# MJ828_-_prod.net
KiCad netlist of a schematic drawn in EAGLE
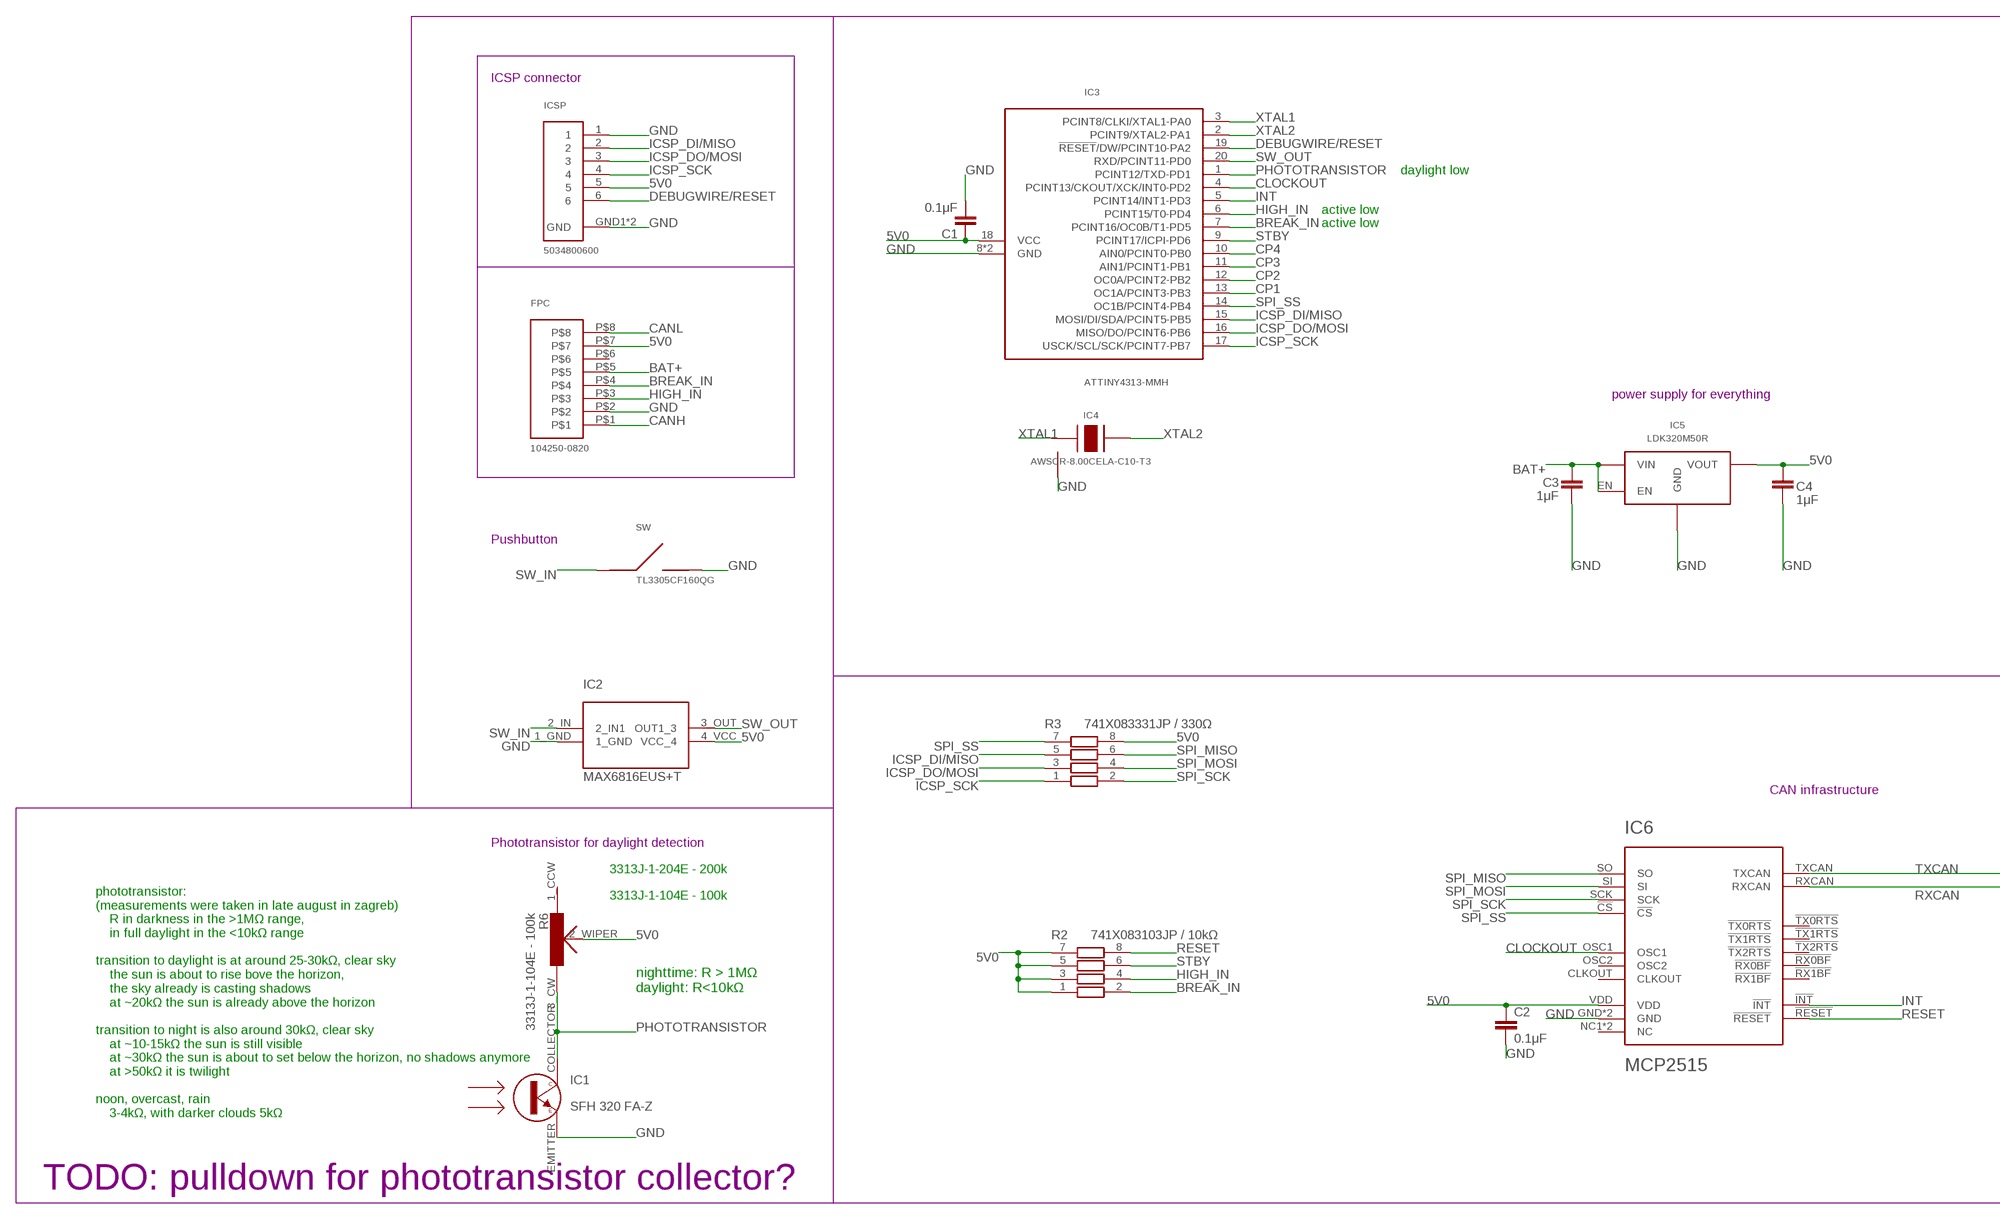
[diagram p0: schematic, sheet 1, part 1 of 2]
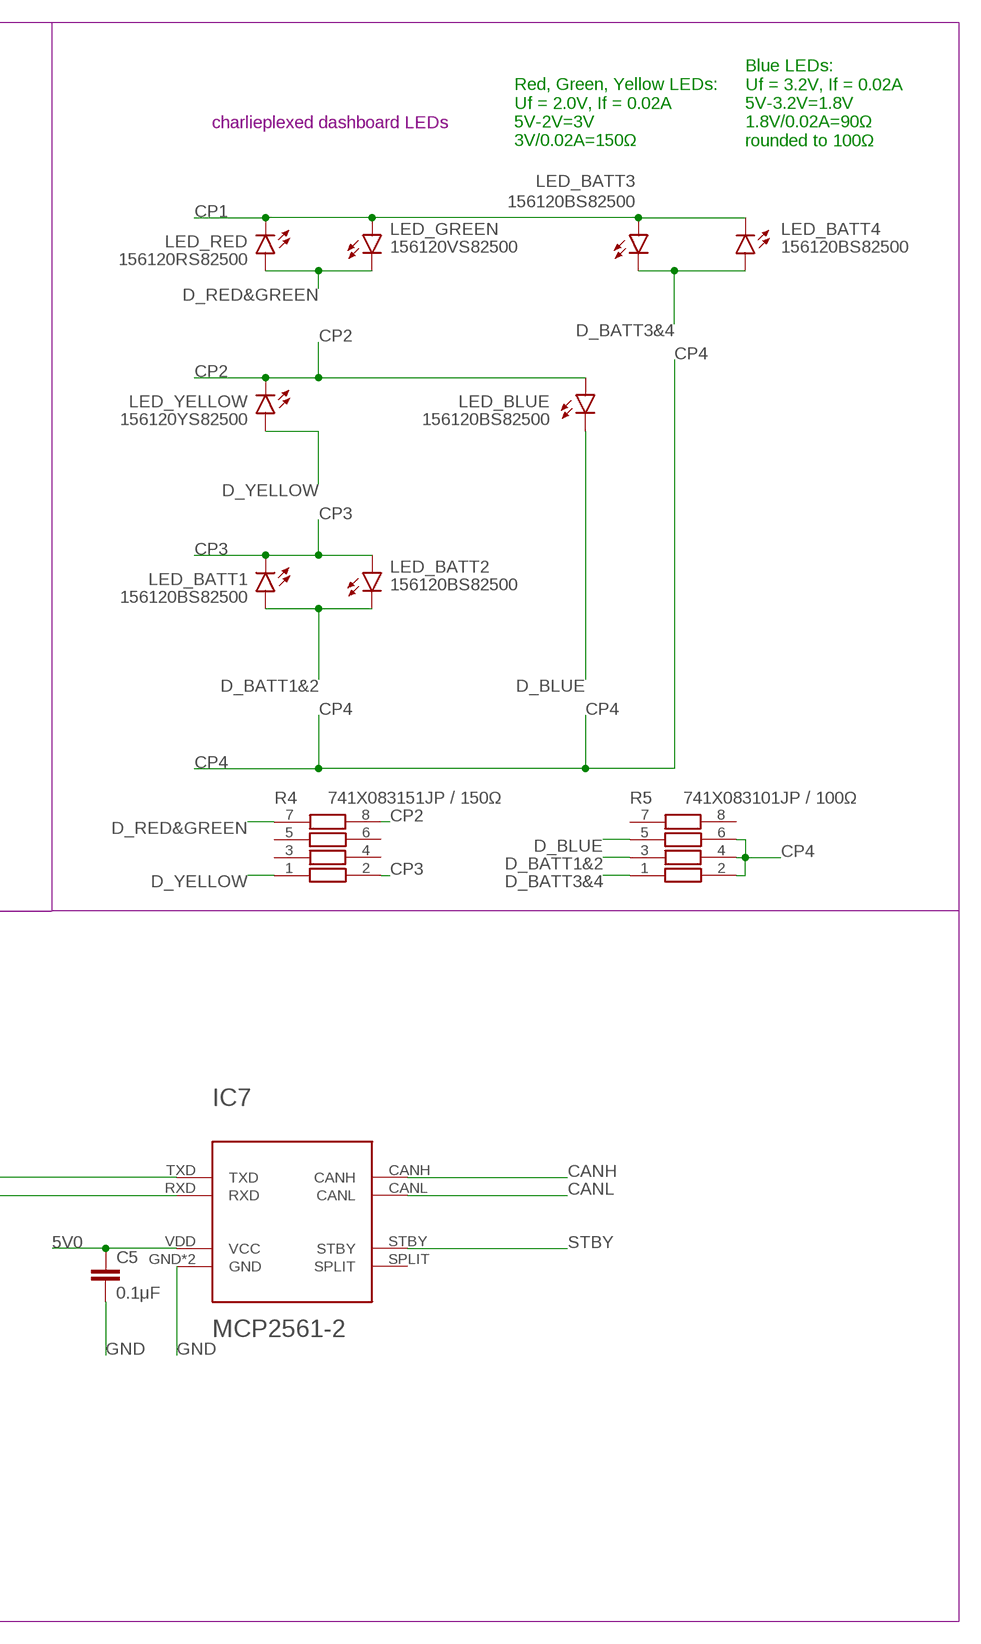
[diagram p1: schematic, sheet 1, part 2 of 2]

(export (version "E")
  (design (tool "Eeschema 10.0.6"))
  (components
    (comp (ref "C1")
      (value "0.1μF")
      (footprint "eagle-import:C0402")
      (libsource (lib "eagle-import") (part "C-EUC0402"))
    )
    (comp (ref "C2")
      (value "0.1μF")
      (footprint "eagle-import:C0402")
      (libsource (lib "eagle-import") (part "C-EUC0402"))
    )
    (comp (ref "C3")
      (value "1μF")
      (footprint "eagle-import:C0402")
      (libsource (lib "eagle-import") (part "C-EUC0402"))
    )
    (comp (ref "C4")
      (value "1μF")
      (footprint "eagle-import:C0402")
      (libsource (lib "eagle-import") (part "C-EUC0402"))
    )
    (comp (ref "C5")
      (value "0.1μF")
      (footprint "eagle-import:C0402")
      (libsource (lib "eagle-import") (part "C-EUC0402"))
    )
    (comp (ref "FPC")
      (value "104250-0820")
      (footprint "eagle-import:SMD")
      (libsource (lib "eagle-import") (part "104250-0820"))
    )
    (comp (ref "IC1")
      (value "SFH 320 FA-Z")
      (footprint "eagle-import:P-LCC-2")
      (libsource (lib "eagle-import") (part "SFH320FA"))
    )
    (comp (ref "IC2")
      (value "MAX6816EUS+T")
      (footprint "eagle-import:4SOT143")
      (libsource (lib "eagle-import") (part "MAX6816"))
    )
    (comp (ref "IC3")
      (value "ATTINY4313-MMH")
      (footprint "eagle-import:VQFN-20")
      (fields (field (name "SPICEPREFIX") "X"))
      (libsource (lib "eagle-import") (part "ATTINY4313VQFN-20"))
    )
    (comp (ref "IC4")
      (value "AWSCR-8.00CELA-C10-T3")
      (footprint "eagle-import:SMT")
      (libsource (lib "eagle-import") (part "PRQV"))
    )
    (comp (ref "IC5")
      (value "LDK320M50R")
      (footprint "eagle-import:SOT-23-5L")
      (libsource (lib "eagle-import") (part "LDK320SOT-23-5L"))
    )
    (comp (ref "IC6")
      (value "MCP2515")
      (footprint "eagle-import:QFN20")
      (libsource (lib "eagle-import") (part "MCP2515-I-ML"))
    )
    (comp (ref "IC7")
      (value "MCP2561-2")
      (footprint "eagle-import:DFN10")
      (libsource (lib "eagle-import") (part "MCP2561-2"))
    )
    (comp (ref "ICSP")
      (value "5034800600")
      (footprint "eagle-import:SMT")
      (libsource (lib "eagle-import") (part "5034800600"))
    )
    (comp (ref "LED_BATT1")
      (value "156120BS82500")
      (footprint "eagle-import:SML1206")
      (libsource (lib "eagle-import") (part "LEDSML1206"))
    )
    (comp (ref "LED_BATT2")
      (value "156120BS82500")
      (footprint "eagle-import:SML1206")
      (libsource (lib "eagle-import") (part "LEDSML1206"))
    )
    (comp (ref "LED_BATT3")
      (value "156120BS82500")
      (footprint "eagle-import:SML1206")
      (libsource (lib "eagle-import") (part "LEDSML1206"))
    )
    (comp (ref "LED_BATT4")
      (value "156120BS82500")
      (footprint "eagle-import:SML1206")
      (libsource (lib "eagle-import") (part "LEDSML1206"))
    )
    (comp (ref "LED_BLUE")
      (value "156120BS82500")
      (footprint "eagle-import:SML1206")
      (libsource (lib "eagle-import") (part "LEDSML1206"))
    )
    (comp (ref "LED_GREEN")
      (value "156120VS82500")
      (footprint "eagle-import:SML1206")
      (libsource (lib "eagle-import") (part "LEDSML1206"))
    )
    (comp (ref "LED_RED")
      (value "156120RS82500")
      (footprint "eagle-import:SML1206")
      (libsource (lib "eagle-import") (part "LEDSML1206"))
    )
    (comp (ref "LED_YELLOW")
      (value "156120YS82500")
      (footprint "eagle-import:SML1206")
      (libsource (lib "eagle-import") (part "LEDSML1206"))
    )
    (comp (ref "R2")
      (value "741X083103JP / 10kΩ")
      (footprint "eagle-import:0402")
      (libsource (lib "eagle-import") (part "741X083331JP"))
    )
    (comp (ref "R3")
      (value "741X083331JP / 330Ω")
      (footprint "eagle-import:0402")
      (libsource (lib "eagle-import") (part "741X083331JP"))
    )
    (comp (ref "R4")
      (value "741X083151JP / 150Ω")
      (footprint "eagle-import:0402")
      (libsource (lib "eagle-import") (part "741X083331JP"))
    )
    (comp (ref "R5")
      (value "741X083101JP / 100Ω")
      (footprint "eagle-import:0402")
      (libsource (lib "eagle-import") (part "741X083331JP"))
    )
    (comp (ref "R6")
      (value "3313J-1-104E - 100k")
      (footprint "eagle-import:3313")
      (libsource (lib "eagle-import") (part "3313"))
    )
    (comp (ref "SW")
      (value "TL3305CF160QG")
      (footprint "eagle-import:SMD")
      (libsource (lib "eagle-import") (part "TL3305-844809"))
    )
  )
  (nets
    (net (code "1") (name "/5V0") (class "Default")
      (node (ref "C1") (pin "1") (pinfunction "1_1") (pintype "passive"))
      (node (ref "C2") (pin "1") (pinfunction "1_1") (pintype "passive"))
      (node (ref "C4") (pin "2") (pinfunction "2_2") (pintype "passive"))
      (node (ref "C5") (pin "1") (pinfunction "1_1") (pintype "passive"))
      (node (ref "FPC") (pin "P$7") (pinfunction "P$7_P$7") (pintype "bidirectional"))
      (node (ref "IC2") (pin "4_VCC") (pinfunction "VCC_4_4_VCC") (pintype "bidirectional"))
      (node (ref "IC3") (pin "18") (pinfunction "VCC_18") (pintype "bidirectional"))
      (node (ref "IC5") (pin "OUT") (pinfunction "VOUT_OUT") (pintype "bidirectional"))
      (node (ref "IC6") (pin "VDD") (pinfunction "VDD_VDD") (pintype "power_in"))
      (node (ref "IC7") (pin "VDD") (pinfunction "VCC_VDD") (pintype "power_in"))
      (node (ref "ICSP") (pin "5") (pinfunction "5_5") (pintype "bidirectional"))
      (node (ref "R2") (pin "1") (pinfunction "1_1") (pintype "bidirectional"))
      (node (ref "R2") (pin "3") (pinfunction "3_3") (pintype "bidirectional"))
      (node (ref "R2") (pin "5") (pinfunction "5_5") (pintype "bidirectional"))
      (node (ref "R2") (pin "7") (pinfunction "7_7") (pintype "bidirectional"))
      (node (ref "R3") (pin "8") (pinfunction "8_8") (pintype "bidirectional"))
      (node (ref "R6") (pin "2_WIPER") (pinfunction "2_WIPER_2_WIPER") (pintype "bidirectional"))
    )
    (net (code "2") (name "/BAT+") (class "Default")
      (node (ref "C3") (pin "1") (pinfunction "1_1") (pintype "passive"))
      (node (ref "FPC") (pin "P$5") (pinfunction "P$5_P$5") (pintype "bidirectional"))
      (node (ref "IC5") (pin "EN") (pinfunction "EN_EN") (pintype "bidirectional"))
      (node (ref "IC5") (pin "IN") (pinfunction "VIN_IN") (pintype "bidirectional"))
    )
    (net (code "3") (name "/BREAK_IN") (class "Default")
      (node (ref "FPC") (pin "P$4") (pinfunction "P$4_P$4") (pintype "bidirectional"))
      (node (ref "IC3") (pin "7") (pinfunction "PCINT16/OC0B/T1-PD5_7") (pintype "bidirectional"))
      (node (ref "R2") (pin "2") (pinfunction "2_2") (pintype "bidirectional"))
    )
    (net (code "4") (name "/CANH") (class "Default")
      (node (ref "FPC") (pin "P$1") (pinfunction "P$1_P$1") (pintype "bidirectional"))
      (node (ref "IC7") (pin "CANH") (pinfunction "CANH_CANH") (pintype "bidirectional"))
    )
    (net (code "5") (name "/CANL") (class "Default")
      (node (ref "FPC") (pin "P$8") (pinfunction "P$8_P$8") (pintype "bidirectional"))
      (node (ref "IC7") (pin "CANL") (pinfunction "CANL_CANL") (pintype "bidirectional"))
    )
    (net (code "6") (name "/CLOCKOUT") (class "Default")
      (node (ref "IC3") (pin "4") (pinfunction "PCINT13/CKOUT/XCK/INT0-PD2_4") (pintype "bidirectional"))
      (node (ref "IC6") (pin "OSC1") (pinfunction "OSC1_OSC1") (pintype "bidirectional"))
    )
    (net (code "7") (name "/CP1") (class "Default")
      (node (ref "IC3") (pin "13") (pinfunction "OC1A/PCINT3-PB3_13") (pintype "bidirectional"))
      (node (ref "LED_BATT3") (pin "A") (pinfunction "A_A") (pintype "passive"))
      (node (ref "LED_BATT4") (pin "C") (pinfunction "C_C") (pintype "passive"))
      (node (ref "LED_GREEN") (pin "A") (pinfunction "A_A") (pintype "passive"))
      (node (ref "LED_RED") (pin "C") (pinfunction "C_C") (pintype "passive"))
    )
    (net (code "8") (name "/CP2") (class "Default")
      (node (ref "IC3") (pin "12") (pinfunction "OC0A/PCINT2-PB2_12") (pintype "bidirectional"))
      (node (ref "LED_BLUE") (pin "A") (pinfunction "A_A") (pintype "passive"))
      (node (ref "LED_YELLOW") (pin "C") (pinfunction "C_C") (pintype "passive"))
      (node (ref "R4") (pin "8") (pinfunction "8_8") (pintype "bidirectional"))
    )
    (net (code "9") (name "/CP3") (class "Default")
      (node (ref "IC3") (pin "11") (pinfunction "AIN1/PCINT1-PB1_11") (pintype "bidirectional"))
      (node (ref "LED_BATT1") (pin "C") (pinfunction "C_C") (pintype "passive"))
      (node (ref "LED_BATT2") (pin "A") (pinfunction "A_A") (pintype "passive"))
      (node (ref "R4") (pin "2") (pinfunction "2_2") (pintype "bidirectional"))
    )
    (net (code "10") (name "/CP4") (class "Default")
      (node (ref "IC3") (pin "10") (pinfunction "AIN0/PCINT0-PB0_10") (pintype "bidirectional"))
      (node (ref "R5") (pin "2") (pinfunction "2_2") (pintype "bidirectional"))
      (node (ref "R5") (pin "4") (pinfunction "4_4") (pintype "bidirectional"))
      (node (ref "R5") (pin "6") (pinfunction "6_6") (pintype "bidirectional"))
    )
    (net (code "11") (name "/DEBUGWIRE{slash}RESET") (class "Default")
      (node (ref "IC3") (pin "19") (pinfunction "~{RESET}/DW/PCINT10-PA2_19") (pintype "bidirectional"))
      (node (ref "ICSP") (pin "6") (pinfunction "6_6") (pintype "bidirectional"))
    )
    (net (code "12") (name "/D_BATT1&2") (class "Default")
      (node (ref "LED_BATT1") (pin "A") (pinfunction "A_A") (pintype "passive"))
      (node (ref "LED_BATT2") (pin "C") (pinfunction "C_C") (pintype "passive"))
      (node (ref "R5") (pin "3") (pinfunction "3_3") (pintype "bidirectional"))
    )
    (net (code "13") (name "/D_BATT3&4") (class "Default")
      (node (ref "LED_BATT3") (pin "C") (pinfunction "C_C") (pintype "passive"))
      (node (ref "LED_BATT4") (pin "A") (pinfunction "A_A") (pintype "passive"))
      (node (ref "R5") (pin "1") (pinfunction "1_1") (pintype "bidirectional"))
    )
    (net (code "14") (name "/D_BLUE") (class "Default")
      (node (ref "LED_BLUE") (pin "C") (pinfunction "C_C") (pintype "passive"))
      (node (ref "R5") (pin "5") (pinfunction "5_5") (pintype "bidirectional"))
    )
    (net (code "15") (name "/D_RED&GREEN") (class "Default")
      (node (ref "LED_GREEN") (pin "C") (pinfunction "C_C") (pintype "passive"))
      (node (ref "LED_RED") (pin "A") (pinfunction "A_A") (pintype "passive"))
      (node (ref "R4") (pin "7") (pinfunction "7_7") (pintype "bidirectional"))
    )
    (net (code "16") (name "/D_YELLOW") (class "Default")
      (node (ref "LED_YELLOW") (pin "A") (pinfunction "A_A") (pintype "passive"))
      (node (ref "R4") (pin "1") (pinfunction "1_1") (pintype "bidirectional"))
    )
    (net (code "17") (name "/GND") (class "Default")
      (node (ref "C1") (pin "2") (pinfunction "2_2") (pintype "passive"))
      (node (ref "C2") (pin "2") (pinfunction "2_2") (pintype "passive"))
      (node (ref "C3") (pin "2") (pinfunction "2_2") (pintype "passive"))
      (node (ref "C4") (pin "1") (pinfunction "1_1") (pintype "passive"))
      (node (ref "C5") (pin "2") (pinfunction "2_2") (pintype "passive"))
      (node (ref "FPC") (pin "P$2") (pinfunction "P$2_P$2") (pintype "bidirectional"))
      (node (ref "IC1") (pin "EMITTER") (pinfunction "EMITTER_EMITTER") (pintype "bidirectional"))
      (node (ref "IC2") (pin "1_GND") (pinfunction "1_GND_1_GND") (pintype "bidirectional"))
      (node (ref "IC3") (pin "8") (pinfunction "GND_8") (pintype "bidirectional"))
      (node (ref "IC3") (pin "GND") (pinfunction "GND_GND") (pintype "bidirectional"))
      (node (ref "IC4") (pin "GND") (pinfunction "GND_GND") (pintype "bidirectional"))
      (node (ref "IC5") (pin "GND") (pinfunction "GND_GND") (pintype "bidirectional"))
      (node (ref "IC6") (pin "GND") (pinfunction "GND_GND") (pintype "power_in"))
      (node (ref "IC6") (pin "GND6") (pinfunction "GND_GND6") (pintype "power_in"))
      (node (ref "IC7") (pin "GND") (pinfunction "GND_GND") (pintype "power_in"))
      (node (ref "IC7") (pin "VSS") (pinfunction "GND_VSS") (pintype "power_in"))
      (node (ref "ICSP") (pin "1") (pinfunction "1_1") (pintype "bidirectional"))
      (node (ref "ICSP") (pin "GND1") (pinfunction "GND_GND1") (pintype "bidirectional"))
      (node (ref "ICSP") (pin "GND2") (pinfunction "GND_GND2") (pintype "bidirectional"))
      (node (ref "SW") (pin "3") (pinfunction "P$2_3") (pintype "bidirectional"))
      (node (ref "SW") (pin "4") (pinfunction "P$2_4") (pintype "bidirectional"))
    )
    (net (code "18") (name "/HIGH_IN") (class "Default")
      (node (ref "FPC") (pin "P$3") (pinfunction "P$3_P$3") (pintype "bidirectional"))
      (node (ref "IC3") (pin "6") (pinfunction "PCINT15/T0-PD4_6") (pintype "bidirectional"))
      (node (ref "R2") (pin "4") (pinfunction "4_4") (pintype "bidirectional"))
    )
    (net (code "19") (name "/ICSP_DI{slash}MISO") (class "Default")
      (node (ref "IC3") (pin "15") (pinfunction "MOSI/DI/SDA/PCINT5-PB5_15") (pintype "bidirectional"))
      (node (ref "ICSP") (pin "2") (pinfunction "2_2") (pintype "bidirectional"))
      (node (ref "R3") (pin "5") (pinfunction "5_5") (pintype "bidirectional"))
    )
    (net (code "20") (name "/ICSP_DO{slash}MOSI") (class "Default")
      (node (ref "IC3") (pin "16") (pinfunction "MISO/DO/PCINT6-PB6_16") (pintype "bidirectional"))
      (node (ref "ICSP") (pin "3") (pinfunction "3_3") (pintype "bidirectional"))
      (node (ref "R3") (pin "3") (pinfunction "3_3") (pintype "bidirectional"))
    )
    (net (code "21") (name "/ICSP_SCK") (class "Default")
      (node (ref "IC3") (pin "17") (pinfunction "USCK/SCL/SCK/PCINT7-PB7_17") (pintype "bidirectional"))
      (node (ref "ICSP") (pin "4") (pinfunction "4_4") (pintype "bidirectional"))
      (node (ref "R3") (pin "1") (pinfunction "1_1") (pintype "bidirectional"))
    )
    (net (code "22") (name "/INT") (class "Default")
      (node (ref "IC3") (pin "5") (pinfunction "PCINT14/INT1-PD3_5") (pintype "bidirectional"))
      (node (ref "IC6") (pin "!INT!") (pinfunction "~{INT}_!INT!") (pintype "bidirectional"))
    )
    (net (code "23") (name "/PHOTOTRANSISTOR") (class "Default")
      (node (ref "IC1") (pin "COLLECTOR") (pinfunction "COLLECTOR_COLLECTOR") (pintype "bidirectional"))
      (node (ref "IC3") (pin "1") (pinfunction "PCINT12/TXD-PD1_1") (pintype "bidirectional"))
      (node (ref "R6") (pin "3_CW") (pinfunction "3_CW_3_CW") (pintype "bidirectional"))
    )
    (net (code "24") (name "/RESET") (class "Default")
      (node (ref "IC6") (pin "!RESET!") (pinfunction "~{RESET}_!RESET!") (pintype "bidirectional"))
      (node (ref "R2") (pin "8") (pinfunction "8_8") (pintype "bidirectional"))
    )
    (net (code "25") (name "/RXCAN") (class "Default")
      (node (ref "IC6") (pin "RXCAN") (pinfunction "RXCAN_RXCAN") (pintype "input"))
      (node (ref "IC7") (pin "RXD") (pinfunction "RXD_RXD") (pintype "output"))
    )
    (net (code "26") (name "/SPI_MISO") (class "Default")
      (node (ref "IC6") (pin "SO") (pinfunction "SO_SO") (pintype "output"))
      (node (ref "R3") (pin "6") (pinfunction "6_6") (pintype "bidirectional"))
    )
    (net (code "27") (name "/SPI_MOSI") (class "Default")
      (node (ref "IC6") (pin "SI") (pinfunction "SI_SI") (pintype "input"))
      (node (ref "R3") (pin "4") (pinfunction "4_4") (pintype "bidirectional"))
    )
    (net (code "28") (name "/SPI_SCK") (class "Default")
      (node (ref "IC6") (pin "SCK") (pinfunction "SCK_SCK") (pintype "bidirectional"))
      (node (ref "R3") (pin "2") (pinfunction "2_2") (pintype "bidirectional"))
    )
    (net (code "29") (name "/SPI_SS") (class "Default")
      (node (ref "IC3") (pin "14") (pinfunction "OC1B/PCINT4-PB4_14") (pintype "bidirectional"))
      (node (ref "IC6") (pin "!CS!") (pinfunction "~{CS}_!CS!") (pintype "bidirectional"))
      (node (ref "R3") (pin "7") (pinfunction "7_7") (pintype "bidirectional"))
    )
    (net (code "30") (name "/STBY") (class "Default")
      (node (ref "IC3") (pin "9") (pinfunction "PCINT17/ICPI-PD6_9") (pintype "bidirectional"))
      (node (ref "IC7") (pin "STBY") (pinfunction "STBY_STBY") (pintype "bidirectional"))
      (node (ref "R2") (pin "6") (pinfunction "6_6") (pintype "bidirectional"))
    )
    (net (code "31") (name "/SW_IN") (class "Default")
      (node (ref "IC2") (pin "2_IN") (pinfunction "2_IN1_2_IN") (pintype "bidirectional"))
      (node (ref "SW") (pin "1") (pinfunction "P$1_1") (pintype "bidirectional"))
      (node (ref "SW") (pin "2") (pinfunction "P$1_2") (pintype "bidirectional"))
    )
    (net (code "32") (name "/SW_OUT") (class "Default")
      (node (ref "IC2") (pin "3_OUT") (pinfunction "OUT1_3_3_OUT") (pintype "bidirectional"))
      (node (ref "IC3") (pin "20") (pinfunction "RXD/PCINT11-PD0_20") (pintype "bidirectional"))
    )
    (net (code "33") (name "/TXCAN") (class "Default")
      (node (ref "IC6") (pin "TXCAN") (pinfunction "TXCAN_TXCAN") (pintype "output"))
      (node (ref "IC7") (pin "TXD") (pinfunction "TXD_TXD") (pintype "input"))
    )
    (net (code "34") (name "/XTAL1") (class "Default")
      (node (ref "IC3") (pin "3") (pinfunction "PCINT8/CLKI/XTAL1-PA0_3") (pintype "bidirectional"))
      (node (ref "IC4") (pin "XTAL1") (pinfunction "XTAL1_XTAL1") (pintype "bidirectional"))
    )
    (net (code "35") (name "/XTAL2") (class "Default")
      (node (ref "IC3") (pin "2") (pinfunction "PCINT9/XTAL2-PA1_2") (pintype "bidirectional"))
      (node (ref "IC4") (pin "XTAL2") (pinfunction "XTAL2_XTAL2") (pintype "bidirectional"))
    )
    (net (code "36") (name "unconnected-(FPC-PadP$6)") (class "Default")
      (node (ref "FPC") (pin "P$6") (pinfunction "P$6_P$6") (pintype "bidirectional"))
    )
    (net (code "37") (name "unconnected-(IC6-NC-PadNC1)") (class "Default")
      (node (ref "IC6") (pin "NC1") (pinfunction "NC_NC1") (pintype "no_connect"))
    )
    (net (code "38") (name "unconnected-(IC6-NC-PadNC2)") (class "Default")
      (node (ref "IC6") (pin "NC2") (pinfunction "NC_NC2") (pintype "no_connect"))
    )
    (net (code "39") (name "unconnected-(IC6-PadCLKOUT)") (class "Default")
      (node (ref "IC6") (pin "CLKOUT") (pinfunction "CLKOUT_CLKOUT") (pintype "bidirectional"))
    )
    (net (code "40") (name "unconnected-(IC6-PadOSC2)") (class "Default")
      (node (ref "IC6") (pin "OSC2") (pinfunction "OSC2_OSC2") (pintype "bidirectional"))
    )
    (net (code "41") (name "unconnected-(IC6-~{RX0BF}-Pad!RX0BF!)") (class "Default")
      (node (ref "IC6") (pin "!RX0BF!") (pinfunction "~{RX0BF}_!RX0BF!") (pintype "bidirectional"))
    )
    (net (code "42") (name "unconnected-(IC6-~{RX1BF}-Pad!RX1BF!)") (class "Default")
      (node (ref "IC6") (pin "!RX1BF!") (pinfunction "~{RX1BF}_!RX1BF!") (pintype "bidirectional"))
    )
    (net (code "43") (name "unconnected-(IC6-~{TX0RTS}-Pad!TX0RTS!)") (class "Default")
      (node (ref "IC6") (pin "!TX0RTS!") (pinfunction "~{TX0RTS}_!TX0RTS!") (pintype "bidirectional"))
    )
    (net (code "44") (name "unconnected-(IC6-~{TX1RTS}-Pad!TX1RTS!)") (class "Default")
      (node (ref "IC6") (pin "!TX1RTS!") (pinfunction "~{TX1RTS}_!TX1RTS!") (pintype "bidirectional"))
    )
    (net (code "45") (name "unconnected-(IC6-~{TX2RTS}-Pad!TX2RTS!)") (class "Default")
      (node (ref "IC6") (pin "!TX2RTS!") (pinfunction "~{TX2RTS}_!TX2RTS!") (pintype "bidirectional"))
    )
    (net (code "46") (name "unconnected-(IC7-PadSPLIT)") (class "Default")
      (node (ref "IC7") (pin "SPLIT") (pinfunction "SPLIT_SPLIT") (pintype "bidirectional"))
    )
    (net (code "47") (name "unconnected-(R4-Pad3)") (class "Default")
      (node (ref "R4") (pin "3") (pinfunction "3_3") (pintype "bidirectional"))
    )
    (net (code "48") (name "unconnected-(R4-Pad4)") (class "Default")
      (node (ref "R4") (pin "4") (pinfunction "4_4") (pintype "bidirectional"))
    )
    (net (code "49") (name "unconnected-(R4-Pad5)") (class "Default")
      (node (ref "R4") (pin "5") (pinfunction "5_5") (pintype "bidirectional"))
    )
    (net (code "50") (name "unconnected-(R4-Pad6)") (class "Default")
      (node (ref "R4") (pin "6") (pinfunction "6_6") (pintype "bidirectional"))
    )
    (net (code "51") (name "unconnected-(R5-Pad7)") (class "Default")
      (node (ref "R5") (pin "7") (pinfunction "7_7") (pintype "bidirectional"))
    )
    (net (code "52") (name "unconnected-(R5-Pad8)") (class "Default")
      (node (ref "R5") (pin "8") (pinfunction "8_8") (pintype "bidirectional"))
    )
    (net (code "53") (name "unconnected-(R6-Pad1_CCW)") (class "Default")
      (node (ref "R6") (pin "1_CCW") (pinfunction "1_CCW_1_CCW") (pintype "bidirectional"))
    )
  )
)
